# transmitter_schematic.net
KiCad netlist of a schematic drawn in EAGLE
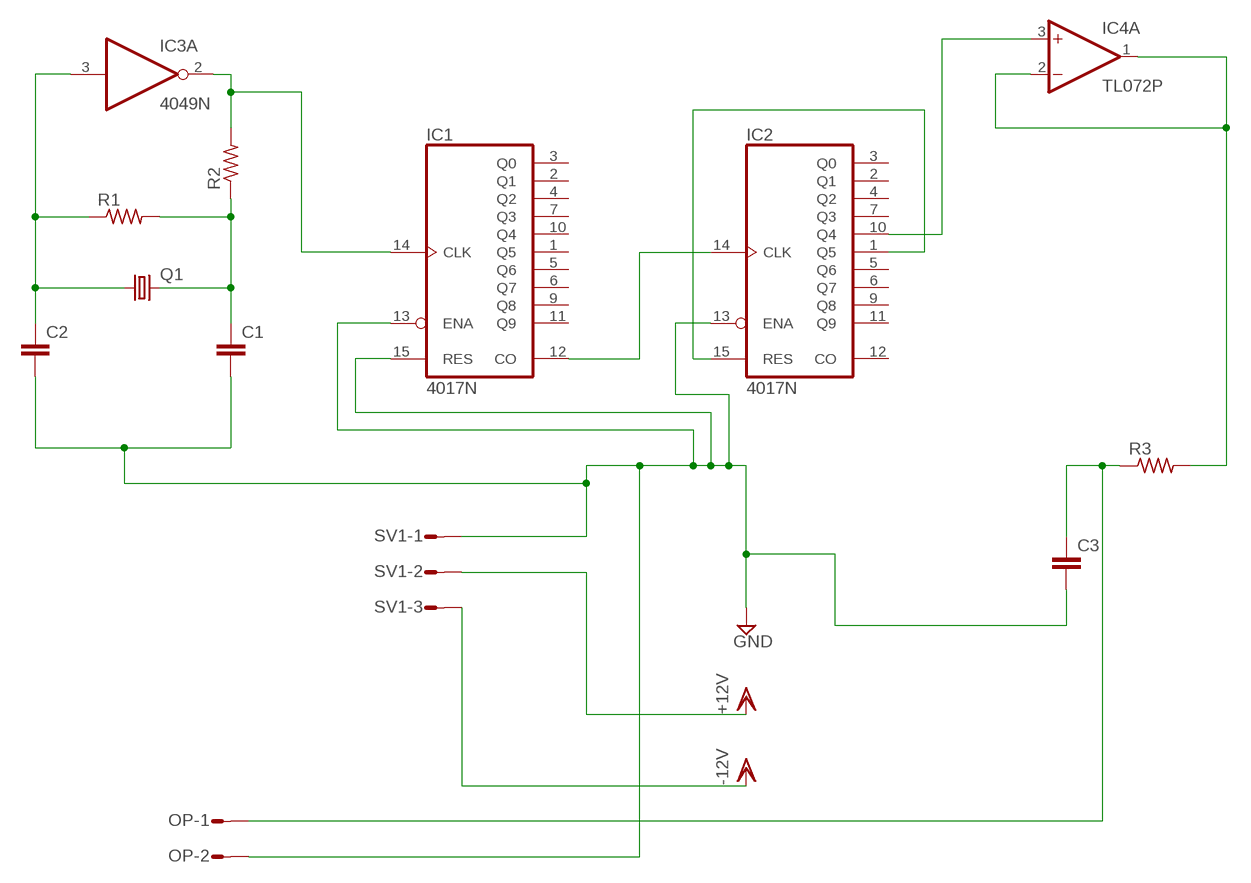
[diagram p0: schematic, sheet 1]

(export (version "E")
  (design (tool "Eeschema 10.0.6"))
  (components
    (comp (ref "C1")
      (value "C5/3.5")
      (footprint "eagle-import:C5B3.5")
      (libsource (lib "eagle-import") (part "C5/3.5"))
    )
    (comp (ref "C2")
      (value "C5/3.5")
      (footprint "eagle-import:C5B3.5")
      (libsource (lib "eagle-import") (part "C5/3.5"))
    )
    (comp (ref "C3")
      (value "C5/3.5")
      (footprint "eagle-import:C5B3.5")
      (libsource (lib "eagle-import") (part "C5/3.5"))
    )
    (comp (ref "IC1")
      (value "4017N")
      (footprint "eagle-import:DIL16")
      (libsource (lib "eagle-import") (part "4017N"))
    )
    (comp (ref "IC2")
      (value "4017N")
      (footprint "eagle-import:DIL16")
      (libsource (lib "eagle-import") (part "4017N"))
    )
    (comp (ref "IC3")
      (value "4049N")
      (footprint "eagle-import:DIL16")
      (libsource (lib "eagle-import") (part "4049N"))
    )
    (comp (ref "IC4")
      (value "TL072P")
      (footprint "eagle-import:DIL08")
      (libsource (lib "eagle-import") (part "TL072P"))
    )
    (comp (ref "OP")
      (value "L02P")
      (footprint "eagle-import:L02P")
      (libsource (lib "eagle-import") (part "L02P"))
    )
    (comp (ref "Q1")
      (value "CRYSTALHC49U-V")
      (footprint "eagle-import:HC49U-V")
      (libsource (lib "eagle-import") (part "CRYSTALHC49U-V"))
    )
    (comp (ref "R1")
      (value "R-US_0207/12")
      (footprint "eagle-import:0207_12")
      (libsource (lib "eagle-import") (part "R-US_0207/12"))
    )
    (comp (ref "R2")
      (value "R-US_0207/12")
      (footprint "eagle-import:0207_12")
      (libsource (lib "eagle-import") (part "R-US_0207/12"))
    )
    (comp (ref "R3")
      (value "R-US_0207/12")
      (footprint "eagle-import:0207_12")
      (libsource (lib "eagle-import") (part "R-US_0207/12"))
    )
    (comp (ref "SV1")
      (value "L03P")
      (footprint "eagle-import:L03P")
      (libsource (lib "eagle-import") (part "L03P"))
    )
  )
  (nets
    (net (code "1") (name "+12V") (class "Default")
      (node (ref "SV1") (pin "2") (pinfunction "S_2") (pintype "passive"))
      (node (ref "SV1") (pin "3") (pinfunction "S_3") (pintype "passive"))
    )
    (net (code "2") (name "GND") (class "Default")
      (node (ref "C1") (pin "2") (pinfunction "2_2") (pintype "passive"))
      (node (ref "C2") (pin "2") (pinfunction "2_2") (pintype "passive"))
      (node (ref "C3") (pin "2") (pinfunction "2_2") (pintype "passive"))
      (node (ref "IC1") (pin "13") (pinfunction "ENA_13") (pintype "input"))
      (node (ref "IC1") (pin "15") (pinfunction "RES_15") (pintype "input"))
      (node (ref "IC2") (pin "13") (pinfunction "ENA_13") (pintype "input"))
      (node (ref "OP") (pin "2") (pinfunction "S_2") (pintype "passive"))
      (node (ref "SV1") (pin "1") (pinfunction "S_1") (pintype "passive"))
    )
    (net (code "3") (name "Net-(C1-Pad1)") (class "Default")
      (node (ref "C1") (pin "1") (pinfunction "1_1") (pintype "passive"))
      (node (ref "Q1") (pin "2") (pinfunction "2_2") (pintype "passive"))
      (node (ref "R1") (pin "2") (pinfunction "2_2") (pintype "passive"))
      (node (ref "R2") (pin "1") (pinfunction "1_1") (pintype "passive"))
    )
    (net (code "4") (name "Net-(IC1A-CLK)") (class "Default")
      (node (ref "IC1") (pin "14") (pinfunction "CLK_14") (pintype "input"))
      (node (ref "IC3") (pin "2") (pinfunction "O_2") (pintype "output"))
      (node (ref "R2") (pin "2") (pinfunction "2_2") (pintype "passive"))
    )
    (net (code "5") (name "Net-(IC1A-CO)") (class "Default")
      (node (ref "IC1") (pin "12") (pinfunction "CO_12") (pintype "output"))
      (node (ref "IC2") (pin "14") (pinfunction "CLK_14") (pintype "input"))
    )
    (net (code "6") (name "Net-(IC2A-Q4)") (class "Default")
      (node (ref "IC2") (pin "10") (pinfunction "Q4_10") (pintype "output"))
      (node (ref "IC4") (pin "3") (pinfunction "+IN_3") (pintype "input"))
    )
    (net (code "7") (name "Net-(IC2A-Q5)") (class "Default")
      (node (ref "IC2") (pin "1") (pinfunction "Q5_1") (pintype "output"))
      (node (ref "IC2") (pin "15") (pinfunction "RES_15") (pintype "input"))
    )
    (net (code "8") (name "Net-(IC3A-I)") (class "Default")
      (node (ref "C2") (pin "1") (pinfunction "1_1") (pintype "passive"))
      (node (ref "IC3") (pin "3") (pinfunction "I_3") (pintype "input"))
      (node (ref "Q1") (pin "1") (pinfunction "1_1") (pintype "passive"))
      (node (ref "R1") (pin "1") (pinfunction "1_1") (pintype "passive"))
    )
    (net (code "9") (name "Net-(IC4A--IN)") (class "Default")
      (node (ref "IC4") (pin "1") (pinfunction "OUT_1") (pintype "output"))
      (node (ref "IC4") (pin "2") (pinfunction "-IN_2") (pintype "input"))
      (node (ref "R3") (pin "2") (pinfunction "2_2") (pintype "passive"))
    )
    (net (code "10") (name "Net-(OPA-S)") (class "Default")
      (node (ref "C3") (pin "1") (pinfunction "1_1") (pintype "passive"))
      (node (ref "OP") (pin "1") (pinfunction "S_1") (pintype "passive"))
      (node (ref "R3") (pin "1") (pinfunction "1_1") (pintype "passive"))
    )
    (net (code "11") (name "unconnected-(IC1A-Q0-Pad3)") (class "Default")
      (node (ref "IC1") (pin "3") (pinfunction "Q0_3") (pintype "output"))
    )
    (net (code "12") (name "unconnected-(IC1A-Q1-Pad2)") (class "Default")
      (node (ref "IC1") (pin "2") (pinfunction "Q1_2") (pintype "output"))
    )
    (net (code "13") (name "unconnected-(IC1A-Q2-Pad4)") (class "Default")
      (node (ref "IC1") (pin "4") (pinfunction "Q2_4") (pintype "output"))
    )
    (net (code "14") (name "unconnected-(IC1A-Q3-Pad7)") (class "Default")
      (node (ref "IC1") (pin "7") (pinfunction "Q3_7") (pintype "output"))
    )
    (net (code "15") (name "unconnected-(IC1A-Q4-Pad10)") (class "Default")
      (node (ref "IC1") (pin "10") (pinfunction "Q4_10") (pintype "output"))
    )
    (net (code "16") (name "unconnected-(IC1A-Q5-Pad1)") (class "Default")
      (node (ref "IC1") (pin "1") (pinfunction "Q5_1") (pintype "output"))
    )
    (net (code "17") (name "unconnected-(IC1A-Q6-Pad5)") (class "Default")
      (node (ref "IC1") (pin "5") (pinfunction "Q6_5") (pintype "output"))
    )
    (net (code "18") (name "unconnected-(IC1A-Q7-Pad6)") (class "Default")
      (node (ref "IC1") (pin "6") (pinfunction "Q7_6") (pintype "output"))
    )
    (net (code "19") (name "unconnected-(IC1A-Q8-Pad9)") (class "Default")
      (node (ref "IC1") (pin "9") (pinfunction "Q8_9") (pintype "output"))
    )
    (net (code "20") (name "unconnected-(IC1A-Q9-Pad11)") (class "Default")
      (node (ref "IC1") (pin "11") (pinfunction "Q9_11") (pintype "output"))
    )
    (net (code "21") (name "unconnected-(IC2A-CO-Pad12)") (class "Default")
      (node (ref "IC2") (pin "12") (pinfunction "CO_12") (pintype "output"))
    )
    (net (code "22") (name "unconnected-(IC2A-Q0-Pad3)") (class "Default")
      (node (ref "IC2") (pin "3") (pinfunction "Q0_3") (pintype "output"))
    )
    (net (code "23") (name "unconnected-(IC2A-Q1-Pad2)") (class "Default")
      (node (ref "IC2") (pin "2") (pinfunction "Q1_2") (pintype "output"))
    )
    (net (code "24") (name "unconnected-(IC2A-Q2-Pad4)") (class "Default")
      (node (ref "IC2") (pin "4") (pinfunction "Q2_4") (pintype "output"))
    )
    (net (code "25") (name "unconnected-(IC2A-Q3-Pad7)") (class "Default")
      (node (ref "IC2") (pin "7") (pinfunction "Q3_7") (pintype "output"))
    )
    (net (code "26") (name "unconnected-(IC2A-Q6-Pad5)") (class "Default")
      (node (ref "IC2") (pin "5") (pinfunction "Q6_5") (pintype "output"))
    )
    (net (code "27") (name "unconnected-(IC2A-Q7-Pad6)") (class "Default")
      (node (ref "IC2") (pin "6") (pinfunction "Q7_6") (pintype "output"))
    )
    (net (code "28") (name "unconnected-(IC2A-Q8-Pad9)") (class "Default")
      (node (ref "IC2") (pin "9") (pinfunction "Q8_9") (pintype "output"))
    )
    (net (code "29") (name "unconnected-(IC2A-Q9-Pad11)") (class "Default")
      (node (ref "IC2") (pin "11") (pinfunction "Q9_11") (pintype "output"))
    )
  )
)
